# mippe_mod_test.net
KiCad netlist of a schematic drawn in EAGLE
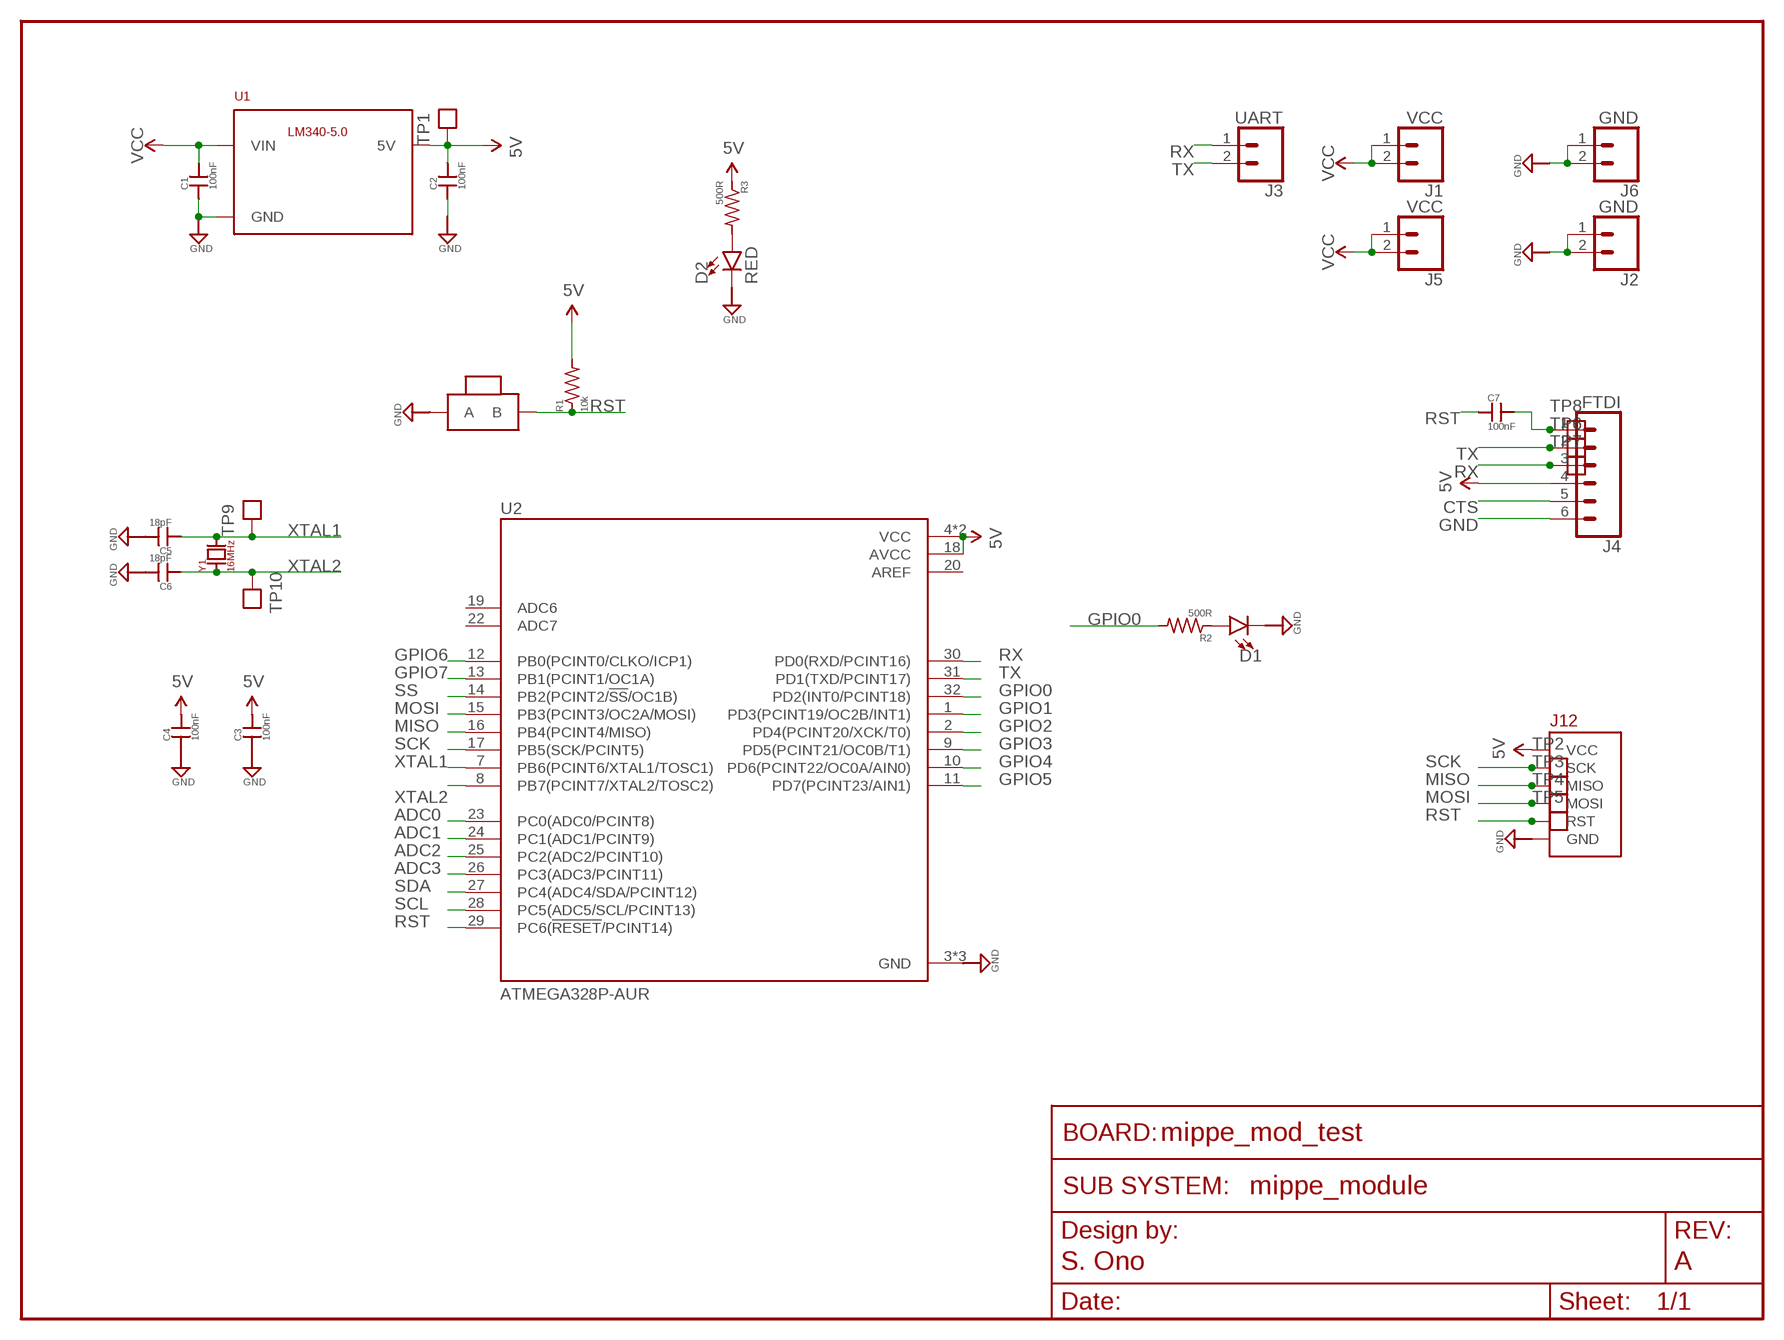
[diagram p0: schematic, sheet 1]

(export (version "E")
  (design (tool "Eeschema 10.0.6"))
  (components
    (comp (ref "C1")
      (value "100nF")
      (footprint "eagle-import:0402-CAP")
      (libsource (lib "eagle-import") (part "CAP0402-CAP"))
    )
    (comp (ref "C2")
      (value "100nF")
      (footprint "eagle-import:0402-CAP")
      (libsource (lib "eagle-import") (part "CAP0402-CAP"))
    )
    (comp (ref "C3")
      (value "100nF")
      (footprint "eagle-import:0402-CAP")
      (libsource (lib "eagle-import") (part "CAP0402-CAP"))
    )
    (comp (ref "C4")
      (value "100nF")
      (footprint "eagle-import:0402-CAP")
      (libsource (lib "eagle-import") (part "CAP0402-CAP"))
    )
    (comp (ref "C5")
      (value "18pF")
      (footprint "eagle-import:0402-CAP")
      (libsource (lib "eagle-import") (part "CAP0402-CAP"))
    )
    (comp (ref "C6")
      (value "18pF")
      (footprint "eagle-import:0402-CAP")
      (libsource (lib "eagle-import") (part "CAP0402-CAP"))
    )
    (comp (ref "C7")
      (value "100nF")
      (footprint "eagle-import:0402-CAP")
      (libsource (lib "eagle-import") (part "CAP0402-CAP"))
    )
    (comp (ref "D1")
      (value "LED0603")
      (footprint "eagle-import:LED-0603")
      (libsource (lib "eagle-import") (part "LED0603"))
    )
    (comp (ref "D2")
      (value "RED")
      (footprint "eagle-import:LED-0603")
      (libsource (lib "eagle-import") (part "LED0603"))
    )
    (comp (ref "J1")
      (value "VCC")
      (footprint "eagle-import:1X02")
      (libsource (lib "eagle-import") (part "CONN_02"))
    )
    (comp (ref "J2")
      (value "GND")
      (footprint "eagle-import:1X02")
      (libsource (lib "eagle-import") (part "CONN_02"))
    )
    (comp (ref "J3")
      (value "UART")
      (footprint "eagle-import:1X02")
      (libsource (lib "eagle-import") (part "CONN_02"))
    )
    (comp (ref "J4")
      (value "FTDI")
      (footprint "eagle-import:1X06_NO_SILK")
      (libsource (lib "eagle-import") (part "CONN_06NO_SILK_FEMALE_PTH"))
    )
    (comp (ref "J5")
      (value "VCC")
      (footprint "eagle-import:1X02")
      (libsource (lib "eagle-import") (part "CONN_02"))
    )
    (comp (ref "J6")
      (value "GND")
      (footprint "eagle-import:1X02")
      (libsource (lib "eagle-import") (part "CONN_02"))
    )
    (comp (ref "J12")
      (value "BURNIN")
      (footprint "eagle-import:BURNIN")
      (libsource (lib "eagle-import") (part "BURNIN"))
    )
    (comp (ref "R1")
      (value "10k")
      (footprint "eagle-import:R0402")
      (libsource (lib "eagle-import") (part "R-US_R0402"))
    )
    (comp (ref "R2")
      (value "500R")
      (footprint "eagle-import:R0402")
      (libsource (lib "eagle-import") (part "R-US_R0402"))
    )
    (comp (ref "R3")
      (value "500R")
      (footprint "eagle-import:R0402")
      (libsource (lib "eagle-import") (part "R-US_R0402"))
    )
    (comp (ref "SW1")
      (value "BTN-PTS810")
      (footprint "eagle-import:BTN_PTS810")
      (libsource (lib "eagle-import") (part "BTN-PTS810"))
    )
    (comp (ref "TP1")
      (value "TEST_POINTTHRU")
      (footprint "eagle-import:TEST_POINT")
      (libsource (lib "eagle-import") (part "TEST_POINTTHRU"))
    )
    (comp (ref "TP2")
      (value "TEST_POINTTHRU")
      (footprint "eagle-import:TEST_POINT")
      (libsource (lib "eagle-import") (part "TEST_POINTTHRU"))
    )
    (comp (ref "TP3")
      (value "TEST_POINTTHRU")
      (footprint "eagle-import:TEST_POINT")
      (libsource (lib "eagle-import") (part "TEST_POINTTHRU"))
    )
    (comp (ref "TP4")
      (value "TEST_POINTTHRU")
      (footprint "eagle-import:TEST_POINT")
      (libsource (lib "eagle-import") (part "TEST_POINTTHRU"))
    )
    (comp (ref "TP5")
      (value "TEST_POINTTHRU")
      (footprint "eagle-import:TEST_POINT")
      (libsource (lib "eagle-import") (part "TEST_POINTTHRU"))
    )
    (comp (ref "TP6")
      (value "TEST_POINTTHRU")
      (footprint "eagle-import:TEST_POINT")
      (libsource (lib "eagle-import") (part "TEST_POINTTHRU"))
    )
    (comp (ref "TP7")
      (value "TEST_POINTTHRU")
      (footprint "eagle-import:TEST_POINT")
      (libsource (lib "eagle-import") (part "TEST_POINTTHRU"))
    )
    (comp (ref "TP8")
      (value "TEST_POINTTHRU")
      (footprint "eagle-import:TEST_POINT")
      (libsource (lib "eagle-import") (part "TEST_POINTTHRU"))
    )
    (comp (ref "TP9")
      (value "TEST_POINTTHRU")
      (footprint "eagle-import:TEST_POINT")
      (libsource (lib "eagle-import") (part "TEST_POINTTHRU"))
    )
    (comp (ref "TP10")
      (value "TEST_POINTTHRU")
      (footprint "eagle-import:TEST_POINT")
      (libsource (lib "eagle-import") (part "TEST_POINTTHRU"))
    )
    (comp (ref "U1")
      (value "LM340MPX-5.0230")
      (footprint "eagle-import:SOT230P700X180-4N")
      (libsource (lib "eagle-import") (part "LM340MPX-5.0230"))
    )
    (comp (ref "U2")
      (value "ATMEGA328P-AUR")
      (footprint "eagle-import:QFP80P900X900X120-32N")
      (fields (field (name "DIGI-KEY_PART_NUMBER") "ATMEGA328P-AURCT-ND") (field (name "MF") "Microchip"))
      (libsource (lib "eagle-import") (part "ATMEGA328P-AUR"))
    )
    (comp (ref "Y1")
      (value "16MHz")
      (footprint "eagle-import:XTAL500X320X130N")
      (libsource (lib "eagle-import") (part "CRYSTAL_SMOL"))
    )
  )
  (nets
    (net (code "1") (name "/ADC0") (class "Default")
      (node (ref "U2") (pin "23") (pinfunction "PC0(ADC0/PCINT8)_23") (pintype "bidirectional"))
    )
    (net (code "2") (name "/ADC1") (class "Default")
      (node (ref "U2") (pin "24") (pinfunction "PC1(ADC1/PCINT9)_24") (pintype "bidirectional"))
    )
    (net (code "3") (name "/ADC2") (class "Default")
      (node (ref "U2") (pin "25") (pinfunction "PC2(ADC2/PCINT10)_25") (pintype "bidirectional"))
    )
    (net (code "4") (name "/ADC3") (class "Default")
      (node (ref "U2") (pin "26") (pinfunction "PC3(ADC3/PCINT11)_26") (pintype "bidirectional"))
    )
    (net (code "5") (name "/AREF") (class "Default")
      (node (ref "U2") (pin "20") (pinfunction "AREF_20") (pintype "power_in"))
    )
    (net (code "6") (name "/CTS") (class "Default")
      (node (ref "J4") (pin "5") (pinfunction "5_5") (pintype "passive"))
    )
    (net (code "7") (name "/GPIO0") (class "Default")
      (node (ref "R2") (pin "2") (pinfunction "2_2") (pintype "passive"))
      (node (ref "U2") (pin "32") (pinfunction "PD2(INT0/PCINT18)_32") (pintype "bidirectional"))
    )
    (net (code "8") (name "/GPIO1") (class "Default")
      (node (ref "U2") (pin "1") (pinfunction "PD3(PCINT19/OC2B/INT1)_1") (pintype "bidirectional"))
    )
    (net (code "9") (name "/GPIO2") (class "Default")
      (node (ref "U2") (pin "2") (pinfunction "PD4(PCINT20/XCK/T0)_2") (pintype "bidirectional"))
    )
    (net (code "10") (name "/GPIO3") (class "Default")
      (node (ref "U2") (pin "9") (pinfunction "PD5(PCINT21/OC0B/T1)_9") (pintype "bidirectional"))
    )
    (net (code "11") (name "/GPIO4") (class "Default")
      (node (ref "U2") (pin "10") (pinfunction "PD6(PCINT22/OC0A/AIN0)_10") (pintype "bidirectional"))
    )
    (net (code "12") (name "/GPIO5") (class "Default")
      (node (ref "U2") (pin "11") (pinfunction "PD7(PCINT23/AIN1)_11") (pintype "bidirectional"))
    )
    (net (code "13") (name "/GPIO6") (class "Default")
      (node (ref "U2") (pin "12") (pinfunction "PB0(PCINT0/CLKO/ICP1)_12") (pintype "bidirectional"))
    )
    (net (code "14") (name "/GPIO7") (class "Default")
      (node (ref "U2") (pin "13") (pinfunction "PB1(PCINT1/OC1A)_13") (pintype "bidirectional"))
    )
    (net (code "15") (name "/MISO") (class "Default")
      (node (ref "J12") (pin "MISO") (pinfunction "MISO_MISO") (pintype "bidirectional"))
      (node (ref "TP3") (pin "1") (pinfunction "P$1_1") (pintype "bidirectional"))
      (node (ref "U2") (pin "16") (pinfunction "PB4(PCINT4/MISO)_16") (pintype "bidirectional"))
    )
    (net (code "16") (name "/MOSI") (class "Default")
      (node (ref "J12") (pin "MOSI") (pinfunction "MOSI_MOSI") (pintype "bidirectional"))
      (node (ref "TP4") (pin "1") (pinfunction "P$1_1") (pintype "bidirectional"))
      (node (ref "U2") (pin "15") (pinfunction "PB3(PCINT3/OC2A/MOSI)_15") (pintype "bidirectional"))
    )
    (net (code "17") (name "/RST") (class "Default")
      (node (ref "C7") (pin "1") (pinfunction "1_1") (pintype "passive"))
      (node (ref "J12") (pin "RST") (pinfunction "RST_RST") (pintype "bidirectional"))
      (node (ref "R1") (pin "1") (pinfunction "1_1") (pintype "passive"))
      (node (ref "SW1") (pin "3") (pinfunction "B_3") (pintype "bidirectional"))
      (node (ref "SW1") (pin "4") (pinfunction "B_4") (pintype "bidirectional"))
      (node (ref "TP5") (pin "1") (pinfunction "P$1_1") (pintype "bidirectional"))
      (node (ref "U2") (pin "29") (pinfunction "PC6(~{RESET}/PCINT14)_29") (pintype "bidirectional"))
    )
    (net (code "18") (name "/RX") (class "Default")
      (node (ref "J3") (pin "1") (pinfunction "1_1") (pintype "passive"))
      (node (ref "J4") (pin "3") (pinfunction "3_3") (pintype "passive"))
      (node (ref "TP7") (pin "1") (pinfunction "P$1_1") (pintype "bidirectional"))
      (node (ref "U2") (pin "30") (pinfunction "PD0(RXD/PCINT16)_30") (pintype "bidirectional"))
    )
    (net (code "19") (name "/SCK") (class "Default")
      (node (ref "J12") (pin "SCK") (pinfunction "SCK_SCK") (pintype "bidirectional"))
      (node (ref "TP2") (pin "1") (pinfunction "P$1_1") (pintype "bidirectional"))
      (node (ref "U2") (pin "17") (pinfunction "PB5(SCK/PCINT5)_17") (pintype "bidirectional"))
    )
    (net (code "20") (name "/SCL") (class "Default")
      (node (ref "U2") (pin "28") (pinfunction "PC5(ADC5/SCL/PCINT13)_28") (pintype "bidirectional"))
    )
    (net (code "21") (name "/SDA") (class "Default")
      (node (ref "U2") (pin "27") (pinfunction "PC4(ADC4/SDA/PCINT12)_27") (pintype "bidirectional"))
    )
    (net (code "22") (name "/SS") (class "Default")
      (node (ref "U2") (pin "14") (pinfunction "PB2(PCINT2/~{SS}/OC1B)_14") (pintype "bidirectional"))
    )
    (net (code "23") (name "/TX") (class "Default")
      (node (ref "J3") (pin "2") (pinfunction "2_2") (pintype "passive"))
      (node (ref "J4") (pin "2") (pinfunction "2_2") (pintype "passive"))
      (node (ref "TP6") (pin "1") (pinfunction "P$1_1") (pintype "bidirectional"))
      (node (ref "U2") (pin "31") (pinfunction "PD1(TXD/PCINT17)_31") (pintype "bidirectional"))
    )
    (net (code "24") (name "/XTAL1") (class "Default")
      (node (ref "C5") (pin "1") (pinfunction "1_1") (pintype "passive"))
      (node (ref "TP9") (pin "1") (pinfunction "P$1_1") (pintype "bidirectional"))
      (node (ref "U2") (pin "7") (pinfunction "PB6(PCINT6/XTAL1/TOSC1)_7") (pintype "bidirectional"))
      (node (ref "Y1") (pin "2") (pinfunction "B_2") (pintype "passive"))
    )
    (net (code "25") (name "/XTAL2") (class "Default")
      (node (ref "C6") (pin "1") (pinfunction "1_1") (pintype "passive"))
      (node (ref "TP10") (pin "1") (pinfunction "P$1_1") (pintype "bidirectional"))
      (node (ref "U2") (pin "8") (pinfunction "PB7(PCINT7/XTAL2/TOSC2)_8") (pintype "bidirectional"))
      (node (ref "Y1") (pin "1") (pinfunction "A_1") (pintype "passive"))
    )
    (net (code "26") (name "5V") (class "Default")
      (node (ref "C2") (pin "2") (pinfunction "2_2") (pintype "passive"))
      (node (ref "C3") (pin "2") (pinfunction "2_2") (pintype "passive"))
      (node (ref "C4") (pin "2") (pinfunction "2_2") (pintype "passive"))
      (node (ref "J12") (pin "3.3V") (pinfunction "VCC_3.3V") (pintype "power_in"))
      (node (ref "J4") (pin "4") (pinfunction "4_4") (pintype "passive"))
      (node (ref "R1") (pin "2") (pinfunction "2_2") (pintype "passive"))
      (node (ref "R3") (pin "1") (pinfunction "1_1") (pintype "passive"))
      (node (ref "TP1") (pin "1") (pinfunction "P$1_1") (pintype "bidirectional"))
      (node (ref "U1") (pin "3") (pinfunction "5V_3") (pintype "power_in"))
      (node (ref "U2") (pin "18") (pinfunction "AVCC_18") (pintype "power_in"))
      (node (ref "U2") (pin "4") (pinfunction "VCC_4") (pintype "power_in"))
      (node (ref "U2") (pin "6") (pinfunction "VCC_6") (pintype "power_in"))
    )
    (net (code "27") (name "GND") (class "Default")
      (node (ref "C1") (pin "1") (pinfunction "1_1") (pintype "passive"))
      (node (ref "C2") (pin "1") (pinfunction "1_1") (pintype "passive"))
      (node (ref "C3") (pin "1") (pinfunction "1_1") (pintype "passive"))
      (node (ref "C4") (pin "1") (pinfunction "1_1") (pintype "passive"))
      (node (ref "C5") (pin "2") (pinfunction "2_2") (pintype "passive"))
      (node (ref "C6") (pin "2") (pinfunction "2_2") (pintype "passive"))
      (node (ref "D1") (pin "C") (pinfunction "C_C") (pintype "passive"))
      (node (ref "D2") (pin "C") (pinfunction "C_C") (pintype "passive"))
      (node (ref "J12") (pin "GND") (pinfunction "GND_GND") (pintype "power_in"))
      (node (ref "J2") (pin "1") (pinfunction "1_1") (pintype "passive"))
      (node (ref "J2") (pin "2") (pinfunction "2_2") (pintype "passive"))
      (node (ref "J4") (pin "6") (pinfunction "6_6") (pintype "passive"))
      (node (ref "J6") (pin "1") (pinfunction "1_1") (pintype "passive"))
      (node (ref "J6") (pin "2") (pinfunction "2_2") (pintype "passive"))
      (node (ref "SW1") (pin "1") (pinfunction "A_1") (pintype "bidirectional"))
      (node (ref "SW1") (pin "2") (pinfunction "A_2") (pintype "bidirectional"))
      (node (ref "U1") (pin "2") (pinfunction "GND_2") (pintype "power_in"))
      (node (ref "U1") (pin "4") (pinfunction "GND_4") (pintype "power_in"))
      (node (ref "U2") (pin "21") (pinfunction "GND_21") (pintype "power_in"))
      (node (ref "U2") (pin "3") (pinfunction "GND_3") (pintype "power_in"))
      (node (ref "U2") (pin "5") (pinfunction "GND_5") (pintype "power_in"))
    )
    (net (code "28") (name "Net-(D1-PadA)") (class "Default")
      (node (ref "D1") (pin "A") (pinfunction "A_A") (pintype "passive"))
      (node (ref "R2") (pin "1") (pinfunction "1_1") (pintype "passive"))
    )
    (net (code "29") (name "Net-(D2-PadA)") (class "Default")
      (node (ref "D2") (pin "A") (pinfunction "A_A") (pintype "passive"))
      (node (ref "R3") (pin "2") (pinfunction "2_2") (pintype "passive"))
    )
    (net (code "30") (name "Net-(TP8-P$1)") (class "Default")
      (node (ref "C7") (pin "2") (pinfunction "2_2") (pintype "passive"))
      (node (ref "J4") (pin "1") (pinfunction "1_1") (pintype "passive"))
      (node (ref "TP8") (pin "1") (pinfunction "P$1_1") (pintype "bidirectional"))
    )
    (net (code "31") (name "VCC") (class "Default")
      (node (ref "C1") (pin "2") (pinfunction "2_2") (pintype "passive"))
      (node (ref "J1") (pin "1") (pinfunction "1_1") (pintype "passive"))
      (node (ref "J1") (pin "2") (pinfunction "2_2") (pintype "passive"))
      (node (ref "J5") (pin "1") (pinfunction "1_1") (pintype "passive"))
      (node (ref "J5") (pin "2") (pinfunction "2_2") (pintype "passive"))
      (node (ref "U1") (pin "1") (pinfunction "VIN_1") (pintype "power_in"))
    )
    (net (code "32") (name "unconnected-(U2-ADC6-Pad19)") (class "Default")
      (node (ref "U2") (pin "19") (pinfunction "ADC6_19") (pintype "input"))
    )
    (net (code "33") (name "unconnected-(U2-ADC7-Pad22)") (class "Default")
      (node (ref "U2") (pin "22") (pinfunction "ADC7_22") (pintype "input"))
    )
  )
)
